# Prog_Adaptor.net
KiCad netlist of a schematic drawn in Altium Designer
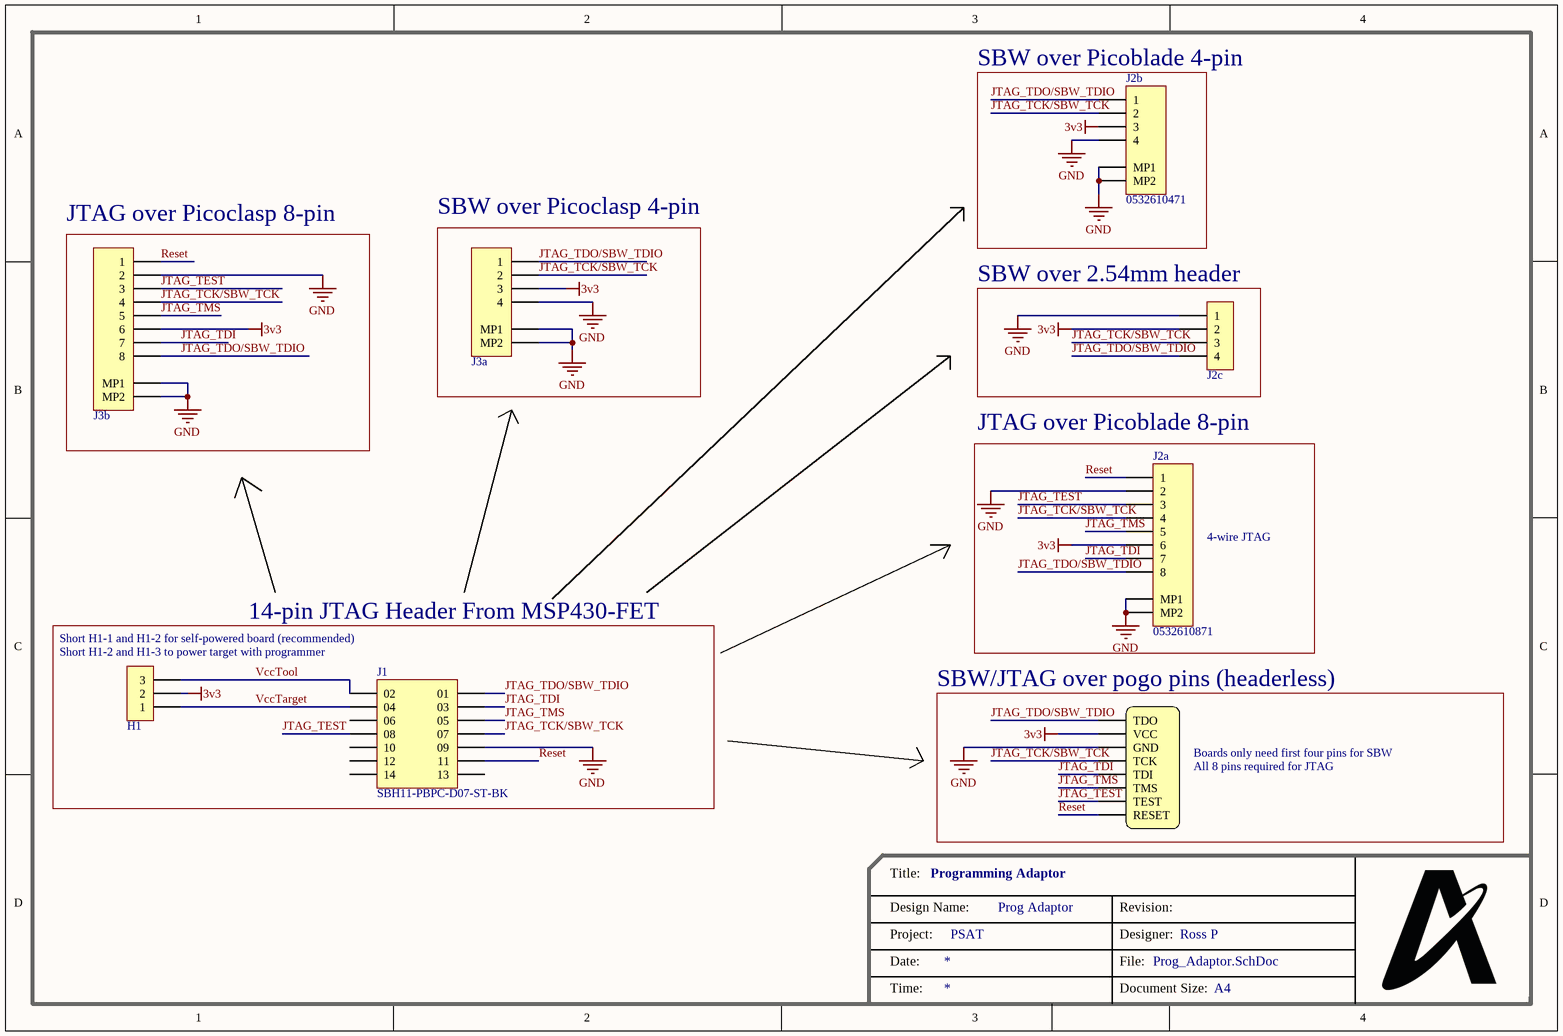
[diagram p0: Prog_Adaptor.SchDoc]

(export (version "E")
  (design (tool "Eeschema 10.0.6"))
  (components
    (comp (ref "H1")
      (value "HDR,2.54mm,1x3")
      (footprint "APSS Connectors:HEADER_2.54MM_1x3PIN")
      (description "Connector - 2.54mm, 1x3-pin")
      (libsource (lib "APSS Connectors") (part "HDR,2.54mm,1x3"))
    )
    (comp (ref "J1")
      (value "SBH11-PBPC-D07-ST-BK")
      (footprint "APSS Prototype Parts:SBH11-PBPC-D07-ST-BK")
      (description "14-pin JTAG Male Header")
      (libsource (lib "APSS Prototype Parts") (part "SBH11-PBPC-D07-ST-BK"))
    )
    (comp (ref "J2a")
      (value "0532610871")
      (footprint "APSS Prototype Parts:MOLEX_0532610871")
      (description "Header - Picoblade 08-pin, SMT, RA")
      (fields (field (name "MF PART NO.") "0532610871"))
      (libsource (lib "APSS Prototype Parts") (part "0532610871"))
    )
    (comp (ref "J2b")
      (value "0532610471")
      (footprint "APSS Prototype Parts:MOLEX_0532610471")
      (description "Header - Picoblade 04-pin, SMT, RA")
      (fields (field (name "MF PART NO.") "0532610471"))
      (libsource (lib "APSS Prototype Parts") (part "0532610471"))
    )
    (comp (ref "J2c")
      (value "HDR,2.54mm,1x4")
      (footprint "APSS Connectors:HEADER_2.54MM_1x4PIN")
      (description "Connector - 2.54mm, 1x4-pin")
      (libsource (lib "APSS Connectors") (part "HDR,2.54mm,1x4"))
    )
    (comp (ref "J2d")
      (value "Headerless Pogo Holes 8-pin")
      (footprint "APSS Connectors:POGO_8_PIN_HEADER")
      (description "Connector - Pogo pin pads, JTAG")
      (libsource (lib "APSS Connectors") (part "Headerless Pogo Holes 8-pin"))
    )
    (comp (ref "J3a")
      (value "5015680407")
      (footprint "APSS Connectors:MOLEX_5015680407")
      (description "Connector - Picoclasp  04-pin, SMT, RA")
      (fields (field (name "APSS STANDARD PART") "APSS Standard"))
      (libsource (lib "APSS Connectors") (part "5015680407"))
    )
    (comp (ref "J3b")
      (value "5015680807")
      (footprint "APSS Connectors:MOLEX_5015680807")
      (description "Connector - Picoclasp  08-pin, SMT, RA")
      (fields (field (name "APSS STANDARD PART") "APSS Standard"))
      (libsource (lib "APSS Connectors") (part "5015680807"))
    )
  )
  (nets
    (net (code "1") (name "/JTAG_TCK{slash}SBW_TCK") (class "Default")
      (node (ref "J1") (pin "07") (pinfunction "07_07") (pintype "passive"))
      (node (ref "J2a") (pin "4") (pinfunction "4_4") (pintype "passive"))
      (node (ref "J2b") (pin "2") (pinfunction "2_2") (pintype "passive"))
      (node (ref "J2c") (pin "3") (pinfunction "3_3") (pintype "passive"))
      (node (ref "J2d") (pin "4") (pinfunction "TCK_4") (pintype "passive"))
      (node (ref "J3a") (pin "2") (pinfunction "2_2") (pintype "passive"))
      (node (ref "J3b") (pin "4") (pinfunction "4_4") (pintype "passive"))
    )
    (net (code "2") (name "/JTAG_TDI") (class "Default")
      (node (ref "J1") (pin "03") (pinfunction "03_03") (pintype "passive"))
      (node (ref "J2a") (pin "7") (pinfunction "7_7") (pintype "passive"))
      (node (ref "J2d") (pin "5") (pinfunction "TDI_5") (pintype "passive"))
      (node (ref "J3b") (pin "7") (pinfunction "7_7") (pintype "passive"))
    )
    (net (code "3") (name "/JTAG_TDO{slash}SBW_TDIO") (class "Default")
      (node (ref "J1") (pin "01") (pinfunction "01_01") (pintype "passive"))
      (node (ref "J2a") (pin "8") (pinfunction "8_8") (pintype "passive"))
      (node (ref "J2b") (pin "1") (pinfunction "1_1") (pintype "passive"))
      (node (ref "J2c") (pin "4") (pinfunction "4_4") (pintype "passive"))
      (node (ref "J2d") (pin "1") (pinfunction "TDO_1") (pintype "passive"))
      (node (ref "J3a") (pin "1") (pinfunction "1_1") (pintype "passive"))
      (node (ref "J3b") (pin "8") (pinfunction "8_8") (pintype "passive"))
    )
    (net (code "4") (name "/JTAG_TEST") (class "Default")
      (node (ref "J1") (pin "08") (pinfunction "08_08") (pintype "passive"))
      (node (ref "J2a") (pin "3") (pinfunction "3_3") (pintype "passive"))
      (node (ref "J2d") (pin "7") (pinfunction "TEST_7") (pintype "passive"))
      (node (ref "J3b") (pin "3") (pinfunction "3_3") (pintype "passive"))
    )
    (net (code "5") (name "/JTAG_TMS") (class "Default")
      (node (ref "J1") (pin "05") (pinfunction "05_05") (pintype "passive"))
      (node (ref "J2a") (pin "5") (pinfunction "5_5") (pintype "passive"))
      (node (ref "J2d") (pin "6") (pinfunction "TMS_6") (pintype "passive"))
      (node (ref "J3b") (pin "5") (pinfunction "5_5") (pintype "passive"))
    )
    (net (code "6") (name "/Reset") (class "Default")
      (node (ref "J1") (pin "11") (pinfunction "11_11") (pintype "passive"))
      (node (ref "J2a") (pin "1") (pinfunction "1_1") (pintype "passive"))
      (node (ref "J2d") (pin "8") (pinfunction "RESET_8") (pintype "passive"))
      (node (ref "J3b") (pin "1") (pinfunction "1_1") (pintype "passive"))
    )
    (net (code "7") (name "/VccTarget") (class "Default")
      (node (ref "H1") (pin "1") (pinfunction "1_1") (pintype "passive"))
      (node (ref "J1") (pin "04") (pinfunction "04_04") (pintype "passive"))
    )
    (net (code "8") (name "/VccTool") (class "Default")
      (node (ref "H1") (pin "3") (pinfunction "3_3") (pintype "passive"))
      (node (ref "J1") (pin "02") (pinfunction "02_02") (pintype "passive"))
    )
    (net (code "9") (name "3v3") (class "Default")
      (node (ref "H1") (pin "2") (pinfunction "2_2") (pintype "passive"))
      (node (ref "J2a") (pin "6") (pinfunction "6_6") (pintype "passive"))
      (node (ref "J2b") (pin "3") (pinfunction "3_3") (pintype "passive"))
      (node (ref "J2c") (pin "2") (pinfunction "2_2") (pintype "passive"))
      (node (ref "J2d") (pin "2") (pinfunction "VCC_2") (pintype "passive"))
      (node (ref "J3a") (pin "3") (pinfunction "3_3") (pintype "passive"))
      (node (ref "J3b") (pin "6") (pinfunction "6_6") (pintype "passive"))
    )
    (net (code "10") (name "GND") (class "Default")
      (node (ref "J1") (pin "09") (pinfunction "09_09") (pintype "passive"))
      (node (ref "J2a") (pin "2") (pinfunction "2_2") (pintype "passive"))
      (node (ref "J2a") (pin "MP1") (pinfunction "MP1_MP1") (pintype "passive"))
      (node (ref "J2a") (pin "MP2") (pinfunction "MP2_MP2") (pintype "passive"))
      (node (ref "J2b") (pin "4") (pinfunction "4_4") (pintype "passive"))
      (node (ref "J2b") (pin "MP1") (pinfunction "MP1_MP1") (pintype "passive"))
      (node (ref "J2b") (pin "MP2") (pinfunction "MP2_MP2") (pintype "passive"))
      (node (ref "J2c") (pin "1") (pinfunction "1_1") (pintype "passive"))
      (node (ref "J2d") (pin "3") (pinfunction "GND_3") (pintype "passive"))
      (node (ref "J3a") (pin "4") (pinfunction "4_4") (pintype "passive"))
      (node (ref "J3a") (pin "MP1") (pinfunction "MP1_MP1") (pintype "passive"))
      (node (ref "J3a") (pin "MP2") (pinfunction "MP2_MP2") (pintype "passive"))
      (node (ref "J3b") (pin "2") (pinfunction "2_2") (pintype "passive"))
      (node (ref "J3b") (pin "MP1") (pinfunction "MP1_MP1") (pintype "passive"))
      (node (ref "J3b") (pin "MP2") (pinfunction "MP2_MP2") (pintype "passive"))
    )
    (net (code "11") (name "unconnected-(J1-Pad06)") (class "Default")
      (node (ref "J1") (pin "06") (pinfunction "06_06") (pintype "passive"))
    )
    (net (code "12") (name "unconnected-(J1-Pad10)") (class "Default")
      (node (ref "J1") (pin "10") (pinfunction "10_10") (pintype "passive"))
    )
    (net (code "13") (name "unconnected-(J1-Pad12)") (class "Default")
      (node (ref "J1") (pin "12") (pinfunction "12_12") (pintype "passive"))
    )
    (net (code "14") (name "unconnected-(J1-Pad13)") (class "Default")
      (node (ref "J1") (pin "13") (pinfunction "13_13") (pintype "passive"))
    )
    (net (code "15") (name "unconnected-(J1-Pad14)") (class "Default")
      (node (ref "J1") (pin "14") (pinfunction "14_14") (pintype "passive"))
    )
  )
)
